# 13_-_SFP_MODULES.net
KiCad netlist of a schematic drawn in Altium Designer
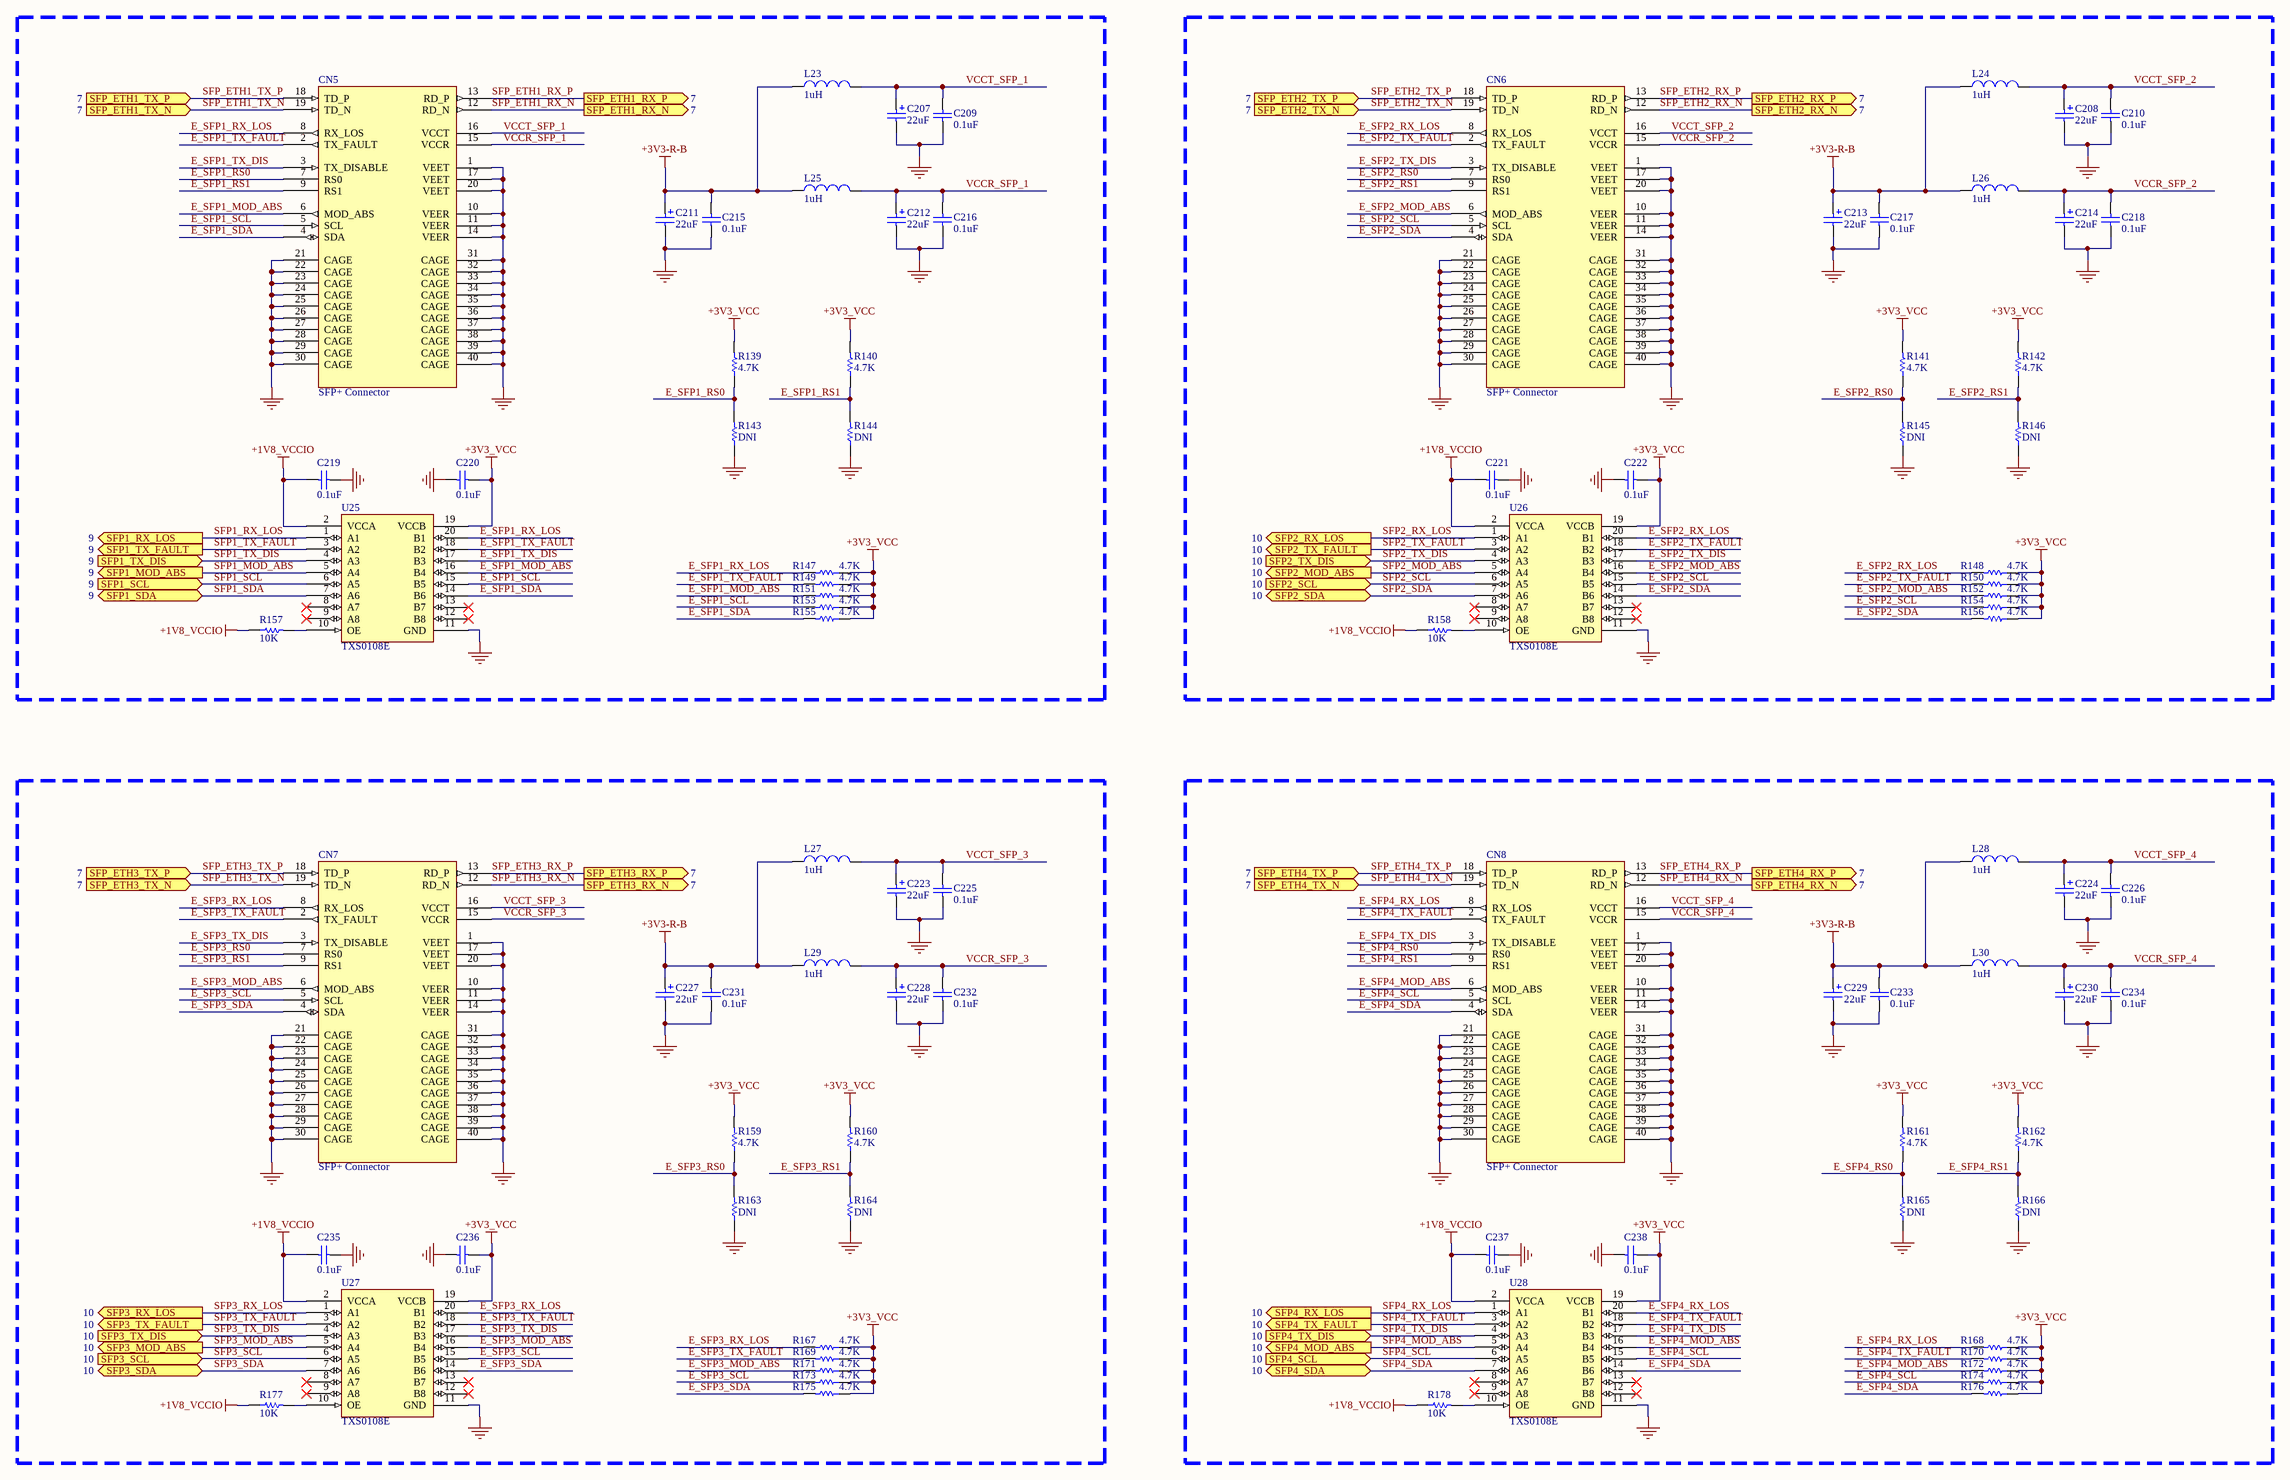
[diagram p0: [13] - SFP+ MODULES.SchDoc]

(export (version "E")
  (design (tool "Eeschema 10.0.6"))
  (components
    (comp (ref "C207")
      (value "22uF")
      (footprint "WCAP-ASLL_8x10.5")
      (description "Aluminium Electrolytic Capacitor")
      (libsource (lib "Passive Components") (part "Cap Aluminium Electrolytic"))
    )
    (comp (ref "C208")
      (value "22uF")
      (footprint "WCAP-ASLL_8x10.5")
      (description "Aluminium Electrolytic Capacitor")
      (libsource (lib "Passive Components") (part "Cap Aluminium Electrolytic"))
    )
    (comp (ref "C209")
      (value "0.1uF")
      (footprint "0402_C")
      (description "Non-Pol SMD Capacitor")
      (libsource (lib "Passive Components") (part "Cap SMD"))
    )
    (comp (ref "C210")
      (value "0.1uF")
      (footprint "0402_C")
      (description "Non-Pol SMD Capacitor")
      (libsource (lib "Passive Components") (part "Cap SMD"))
    )
    (comp (ref "C211")
      (value "22uF")
      (footprint "WCAP-ASLL_8x10.5")
      (description "Aluminium Electrolytic Capacitor")
      (libsource (lib "Passive Components") (part "Cap Aluminium Electrolytic"))
    )
    (comp (ref "C212")
      (value "22uF")
      (footprint "WCAP-ASLL_8x10.5")
      (description "Aluminium Electrolytic Capacitor")
      (libsource (lib "Passive Components") (part "Cap Aluminium Electrolytic"))
    )
    (comp (ref "C213")
      (value "22uF")
      (footprint "WCAP-ASLL_8x10.5")
      (description "Aluminium Electrolytic Capacitor")
      (libsource (lib "Passive Components") (part "Cap Aluminium Electrolytic"))
    )
    (comp (ref "C214")
      (value "22uF")
      (footprint "WCAP-ASLL_8x10.5")
      (description "Aluminium Electrolytic Capacitor")
      (libsource (lib "Passive Components") (part "Cap Aluminium Electrolytic"))
    )
    (comp (ref "C215")
      (value "0.1uF")
      (footprint "0402_C")
      (description "Non-Pol SMD Capacitor")
      (libsource (lib "Passive Components") (part "Cap SMD"))
    )
    (comp (ref "C216")
      (value "0.1uF")
      (footprint "0402_C")
      (description "Non-Pol SMD Capacitor")
      (libsource (lib "Passive Components") (part "Cap SMD"))
    )
    (comp (ref "C217")
      (value "0.1uF")
      (footprint "0402_C")
      (description "Non-Pol SMD Capacitor")
      (libsource (lib "Passive Components") (part "Cap SMD"))
    )
    (comp (ref "C218")
      (value "0.1uF")
      (footprint "0402_C")
      (description "Non-Pol SMD Capacitor")
      (libsource (lib "Passive Components") (part "Cap SMD"))
    )
    (comp (ref "C219")
      (value "0.1uF")
      (footprint "0402_C")
      (description "Non-Pol SMD Capacitor")
      (libsource (lib "Passive Components") (part "Cap SMD"))
    )
    (comp (ref "C220")
      (value "0.1uF")
      (footprint "0402_C")
      (description "Non-Pol SMD Capacitor")
      (libsource (lib "Passive Components") (part "Cap SMD"))
    )
    (comp (ref "C221")
      (value "0.1uF")
      (footprint "0402_C")
      (description "Non-Pol SMD Capacitor")
      (libsource (lib "Passive Components") (part "Cap SMD"))
    )
    (comp (ref "C222")
      (value "0.1uF")
      (footprint "0402_C")
      (description "Non-Pol SMD Capacitor")
      (libsource (lib "Passive Components") (part "Cap SMD"))
    )
    (comp (ref "C223")
      (value "22uF")
      (footprint "WCAP-ASLL_8x10.5")
      (description "Aluminium Electrolytic Capacitor")
      (libsource (lib "Passive Components") (part "Cap Aluminium Electrolytic"))
    )
    (comp (ref "C224")
      (value "22uF")
      (footprint "WCAP-ASLL_8x10.5")
      (description "Aluminium Electrolytic Capacitor")
      (libsource (lib "Passive Components") (part "Cap Aluminium Electrolytic"))
    )
    (comp (ref "C225")
      (value "0.1uF")
      (footprint "0402_C")
      (description "Non-Pol SMD Capacitor")
      (libsource (lib "Passive Components") (part "Cap SMD"))
    )
    (comp (ref "C226")
      (value "0.1uF")
      (footprint "0402_C")
      (description "Non-Pol SMD Capacitor")
      (libsource (lib "Passive Components") (part "Cap SMD"))
    )
    (comp (ref "C227")
      (value "22uF")
      (footprint "WCAP-ASLL_8x10.5")
      (description "Aluminium Electrolytic Capacitor")
      (libsource (lib "Passive Components") (part "Cap Aluminium Electrolytic"))
    )
    (comp (ref "C228")
      (value "22uF")
      (footprint "WCAP-ASLL_8x10.5")
      (description "Aluminium Electrolytic Capacitor")
      (libsource (lib "Passive Components") (part "Cap Aluminium Electrolytic"))
    )
    (comp (ref "C229")
      (value "22uF")
      (footprint "WCAP-ASLL_8x10.5")
      (description "Aluminium Electrolytic Capacitor")
      (libsource (lib "Passive Components") (part "Cap Aluminium Electrolytic"))
    )
    (comp (ref "C230")
      (value "22uF")
      (footprint "WCAP-ASLL_8x10.5")
      (description "Aluminium Electrolytic Capacitor")
      (libsource (lib "Passive Components") (part "Cap Aluminium Electrolytic"))
    )
    (comp (ref "C231")
      (value "0.1uF")
      (footprint "0402_C")
      (description "Non-Pol SMD Capacitor")
      (libsource (lib "Passive Components") (part "Cap SMD"))
    )
    (comp (ref "C232")
      (value "0.1uF")
      (footprint "0402_C")
      (description "Non-Pol SMD Capacitor")
      (libsource (lib "Passive Components") (part "Cap SMD"))
    )
    (comp (ref "C233")
      (value "0.1uF")
      (footprint "0402_C")
      (description "Non-Pol SMD Capacitor")
      (libsource (lib "Passive Components") (part "Cap SMD"))
    )
    (comp (ref "C234")
      (value "0.1uF")
      (footprint "0402_C")
      (description "Non-Pol SMD Capacitor")
      (libsource (lib "Passive Components") (part "Cap SMD"))
    )
    (comp (ref "C235")
      (value "0.1uF")
      (footprint "0402_C")
      (description "Non-Pol SMD Capacitor")
      (libsource (lib "Passive Components") (part "Cap SMD"))
    )
    (comp (ref "C236")
      (value "0.1uF")
      (footprint "0402_C")
      (description "Non-Pol SMD Capacitor")
      (libsource (lib "Passive Components") (part "Cap SMD"))
    )
    (comp (ref "C237")
      (value "0.1uF")
      (footprint "0402_C")
      (description "Non-Pol SMD Capacitor")
      (libsource (lib "Passive Components") (part "Cap SMD"))
    )
    (comp (ref "C238")
      (value "0.1uF")
      (footprint "0402_C")
      (description "Non-Pol SMD Capacitor")
      (libsource (lib "Passive Components") (part "Cap SMD"))
    )
    (comp (ref "CN5")
      (value "SFP+ Connector")
      (description "SFP+ Host Connector, Z-Axis Pluggable, Right-Angle, Surface Mount, 20 Circuits , and EMI Cage")
      (libsource (lib "Project_schlib") (part "SFP+ Connector"))
    )
    (comp (ref "CN6")
      (value "SFP+ Connector")
      (description "SFP+ Host Connector, Z-Axis Pluggable, Right-Angle, Surface Mount, 20 Circuits , and EMI Cage")
      (libsource (lib "Project_schlib") (part "SFP+ Connector"))
    )
    (comp (ref "CN7")
      (value "SFP+ Connector")
      (description "SFP+ Host Connector, Z-Axis Pluggable, Right-Angle, Surface Mount, 20 Circuits , and EMI Cage")
      (libsource (lib "Project_schlib") (part "SFP+ Connector"))
    )
    (comp (ref "CN8")
      (value "SFP+ Connector")
      (description "SFP+ Host Connector, Z-Axis Pluggable, Right-Angle, Surface Mount, 20 Circuits , and EMI Cage")
      (libsource (lib "Project_schlib") (part "SFP+ Connector"))
    )
    (comp (ref "L23")
      (value "1uH")
      (footprint "0402_R")
      (description "Inductor SMD")
      (libsource (lib "Passive Components") (part "Inductor"))
    )
    (comp (ref "L24")
      (value "1uH")
      (footprint "0402_R")
      (description "Inductor SMD")
      (libsource (lib "Passive Components") (part "Inductor"))
    )
    (comp (ref "L25")
      (value "1uH")
      (footprint "0402_R")
      (description "Inductor SMD")
      (libsource (lib "Passive Components") (part "Inductor"))
    )
    (comp (ref "L26")
      (value "1uH")
      (footprint "0402_R")
      (description "Inductor SMD")
      (libsource (lib "Passive Components") (part "Inductor"))
    )
    (comp (ref "L27")
      (value "1uH")
      (footprint "0402_R")
      (description "Inductor SMD")
      (libsource (lib "Passive Components") (part "Inductor"))
    )
    (comp (ref "L28")
      (value "1uH")
      (footprint "0402_R")
      (description "Inductor SMD")
      (libsource (lib "Passive Components") (part "Inductor"))
    )
    (comp (ref "L29")
      (value "1uH")
      (footprint "0402_R")
      (description "Inductor SMD")
      (libsource (lib "Passive Components") (part "Inductor"))
    )
    (comp (ref "L30")
      (value "1uH")
      (footprint "0402_R")
      (description "Inductor SMD")
      (libsource (lib "Passive Components") (part "Inductor"))
    )
    (comp (ref "R139")
      (value "4.7K")
      (footprint "0805_R")
      (description "SMD Resistor")
      (fields (field (name "TOLERANCE") "5%"))
      (libsource (lib "Passive Components") (part "Res SMD"))
    )
    (comp (ref "R140")
      (value "4.7K")
      (footprint "0805_R")
      (description "SMD Resistor")
      (fields (field (name "TOLERANCE") "5%"))
      (libsource (lib "Passive Components") (part "Res SMD"))
    )
    (comp (ref "R141")
      (value "4.7K")
      (footprint "0805_R")
      (description "SMD Resistor")
      (fields (field (name "TOLERANCE") "5%"))
      (libsource (lib "Passive Components") (part "Res SMD"))
    )
    (comp (ref "R142")
      (value "4.7K")
      (footprint "0805_R")
      (description "SMD Resistor")
      (fields (field (name "TOLERANCE") "5%"))
      (libsource (lib "Passive Components") (part "Res SMD"))
    )
    (comp (ref "R143")
      (value "DNI")
      (footprint "0805_R")
      (description "SMD Resistor")
      (fields (field (name "TOLERANCE") "5%"))
      (libsource (lib "Passive Components") (part "Res SMD"))
    )
    (comp (ref "R144")
      (value "DNI")
      (footprint "0805_R")
      (description "SMD Resistor")
      (fields (field (name "TOLERANCE") "5%"))
      (libsource (lib "Passive Components") (part "Res SMD"))
    )
    (comp (ref "R145")
      (value "DNI")
      (footprint "0805_R")
      (description "SMD Resistor")
      (fields (field (name "TOLERANCE") "5%"))
      (libsource (lib "Passive Components") (part "Res SMD"))
    )
    (comp (ref "R146")
      (value "DNI")
      (footprint "0805_R")
      (description "SMD Resistor")
      (fields (field (name "TOLERANCE") "5%"))
      (libsource (lib "Passive Components") (part "Res SMD"))
    )
    (comp (ref "R147")
      (value "4.7K")
      (footprint "0805_R")
      (description "SMD Resistor")
      (fields (field (name "TOLERANCE") "5%"))
      (libsource (lib "Passive Components") (part "Res SMD"))
    )
    (comp (ref "R148")
      (value "4.7K")
      (footprint "0805_R")
      (description "SMD Resistor")
      (fields (field (name "TOLERANCE") "5%"))
      (libsource (lib "Passive Components") (part "Res SMD"))
    )
    (comp (ref "R149")
      (value "4.7K")
      (footprint "0805_R")
      (description "SMD Resistor")
      (fields (field (name "TOLERANCE") "5%"))
      (libsource (lib "Passive Components") (part "Res SMD"))
    )
    (comp (ref "R150")
      (value "4.7K")
      (footprint "0805_R")
      (description "SMD Resistor")
      (fields (field (name "TOLERANCE") "5%"))
      (libsource (lib "Passive Components") (part "Res SMD"))
    )
    (comp (ref "R151")
      (value "4.7K")
      (footprint "0805_R")
      (description "SMD Resistor")
      (fields (field (name "TOLERANCE") "5%"))
      (libsource (lib "Passive Components") (part "Res SMD"))
    )
    (comp (ref "R152")
      (value "4.7K")
      (footprint "0805_R")
      (description "SMD Resistor")
      (fields (field (name "TOLERANCE") "5%"))
      (libsource (lib "Passive Components") (part "Res SMD"))
    )
    (comp (ref "R153")
      (value "4.7K")
      (footprint "0805_R")
      (description "SMD Resistor")
      (fields (field (name "TOLERANCE") "5%"))
      (libsource (lib "Passive Components") (part "Res SMD"))
    )
    (comp (ref "R154")
      (value "4.7K")
      (footprint "0805_R")
      (description "SMD Resistor")
      (fields (field (name "TOLERANCE") "5%"))
      (libsource (lib "Passive Components") (part "Res SMD"))
    )
    (comp (ref "R155")
      (value "4.7K")
      (footprint "0805_R")
      (description "SMD Resistor")
      (fields (field (name "TOLERANCE") "5%"))
      (libsource (lib "Passive Components") (part "Res SMD"))
    )
    (comp (ref "R156")
      (value "4.7K")
      (footprint "0805_R")
      (description "SMD Resistor")
      (fields (field (name "TOLERANCE") "5%"))
      (libsource (lib "Passive Components") (part "Res SMD"))
    )
    (comp (ref "R157")
      (value "10K")
      (footprint "0402_R")
      (description "SMD Resistor")
      (fields (field (name "TOLERANCE") "5%"))
      (libsource (lib "Passive Components") (part "Res SMD"))
    )
    (comp (ref "R158")
      (value "10K")
      (footprint "0402_R")
      (description "SMD Resistor")
      (fields (field (name "TOLERANCE") "5%"))
      (libsource (lib "Passive Components") (part "Res SMD"))
    )
    (comp (ref "R159")
      (value "4.7K")
      (footprint "0805_R")
      (description "SMD Resistor")
      (fields (field (name "TOLERANCE") "5%"))
      (libsource (lib "Passive Components") (part "Res SMD"))
    )
    (comp (ref "R160")
      (value "4.7K")
      (footprint "0805_R")
      (description "SMD Resistor")
      (fields (field (name "TOLERANCE") "5%"))
      (libsource (lib "Passive Components") (part "Res SMD"))
    )
    (comp (ref "R161")
      (value "4.7K")
      (footprint "0805_R")
      (description "SMD Resistor")
      (fields (field (name "TOLERANCE") "5%"))
      (libsource (lib "Passive Components") (part "Res SMD"))
    )
    (comp (ref "R162")
      (value "4.7K")
      (footprint "0805_R")
      (description "SMD Resistor")
      (fields (field (name "TOLERANCE") "5%"))
      (libsource (lib "Passive Components") (part "Res SMD"))
    )
    (comp (ref "R163")
      (value "DNI")
      (footprint "0805_R")
      (description "SMD Resistor")
      (fields (field (name "TOLERANCE") "5%"))
      (libsource (lib "Passive Components") (part "Res SMD"))
    )
    (comp (ref "R164")
      (value "DNI")
      (footprint "0805_R")
      (description "SMD Resistor")
      (fields (field (name "TOLERANCE") "5%"))
      (libsource (lib "Passive Components") (part "Res SMD"))
    )
    (comp (ref "R165")
      (value "DNI")
      (footprint "0805_R")
      (description "SMD Resistor")
      (fields (field (name "TOLERANCE") "5%"))
      (libsource (lib "Passive Components") (part "Res SMD"))
    )
    (comp (ref "R166")
      (value "DNI")
      (footprint "0805_R")
      (description "SMD Resistor")
      (fields (field (name "TOLERANCE") "5%"))
      (libsource (lib "Passive Components") (part "Res SMD"))
    )
    (comp (ref "R167")
      (value "4.7K")
      (footprint "0805_R")
      (description "SMD Resistor")
      (fields (field (name "TOLERANCE") "5%"))
      (libsource (lib "Passive Components") (part "Res SMD"))
    )
    (comp (ref "R168")
      (value "4.7K")
      (footprint "0805_R")
      (description "SMD Resistor")
      (fields (field (name "TOLERANCE") "5%"))
      (libsource (lib "Passive Components") (part "Res SMD"))
    )
    (comp (ref "R169")
      (value "4.7K")
      (footprint "0805_R")
      (description "SMD Resistor")
      (fields (field (name "TOLERANCE") "5%"))
      (libsource (lib "Passive Components") (part "Res SMD"))
    )
    (comp (ref "R170")
      (value "4.7K")
      (footprint "0805_R")
      (description "SMD Resistor")
      (fields (field (name "TOLERANCE") "5%"))
      (libsource (lib "Passive Components") (part "Res SMD"))
    )
    (comp (ref "R171")
      (value "4.7K")
      (footprint "0805_R")
      (description "SMD Resistor")
      (fields (field (name "TOLERANCE") "5%"))
      (libsource (lib "Passive Components") (part "Res SMD"))
    )
    (comp (ref "R172")
      (value "4.7K")
      (footprint "0805_R")
      (description "SMD Resistor")
      (fields (field (name "TOLERANCE") "5%"))
      (libsource (lib "Passive Components") (part "Res SMD"))
    )
    (comp (ref "R173")
      (value "4.7K")
      (footprint "0805_R")
      (description "SMD Resistor")
      (fields (field (name "TOLERANCE") "5%"))
      (libsource (lib "Passive Components") (part "Res SMD"))
    )
    (comp (ref "R174")
      (value "4.7K")
      (footprint "0805_R")
      (description "SMD Resistor")
      (fields (field (name "TOLERANCE") "5%"))
      (libsource (lib "Passive Components") (part "Res SMD"))
    )
    (comp (ref "R175")
      (value "4.7K")
      (footprint "0805_R")
      (description "SMD Resistor")
      (fields (field (name "TOLERANCE") "5%"))
      (libsource (lib "Passive Components") (part "Res SMD"))
    )
    (comp (ref "R176")
      (value "4.7K")
      (footprint "0805_R")
      (description "SMD Resistor")
      (fields (field (name "TOLERANCE") "5%"))
      (libsource (lib "Passive Components") (part "Res SMD"))
    )
    (comp (ref "R177")
      (value "10K")
      (footprint "0402_R")
      (description "SMD Resistor")
      (fields (field (name "TOLERANCE") "5%"))
      (libsource (lib "Passive Components") (part "Res SMD"))
    )
    (comp (ref "R178")
      (value "10K")
      (footprint "0402_R")
      (description "SMD Resistor")
      (fields (field (name "TOLERANCE") "5%"))
      (libsource (lib "Passive Components") (part "Res SMD"))
    )
    (comp (ref "U25")
      (value "TXS0108E")
      (description "8-Bit Bidirectional Voltage-Level Translator for Open-Drain and Push-Pull Applications")
      (fields (field (name "MANUFACTURER PART NUM") "TXS0108EPWR"))
      (libsource (lib "Project_schlib") (part "TXS0108E"))
    )
    (comp (ref "U26")
      (value "TXS0108E")
      (description "8-Bit Bidirectional Voltage-Level Translator for Open-Drain and Push-Pull Applications")
      (fields (field (name "MANUFACTURER PART NUM") "TXS0108EPWR"))
      (libsource (lib "Project_schlib") (part "TXS0108E"))
    )
    (comp (ref "U27")
      (value "TXS0108E")
      (description "8-Bit Bidirectional Voltage-Level Translator for Open-Drain and Push-Pull Applications")
      (fields (field (name "MANUFACTURER PART NUM") "TXS0108EPWR"))
      (libsource (lib "Project_schlib") (part "TXS0108E"))
    )
    (comp (ref "U28")
      (value "TXS0108E")
      (description "8-Bit Bidirectional Voltage-Level Translator for Open-Drain and Push-Pull Applications")
      (fields (field (name "MANUFACTURER PART NUM") "TXS0108EPWR"))
      (libsource (lib "Project_schlib") (part "TXS0108E"))
    )
  )
  (nets
    (net (code "1") (name "+1V8_VCCIO") (class "Default")
      (node (ref "C219") (pin "2") (pinfunction "2_2") (pintype "passive"))
      (node (ref "C221") (pin "2") (pinfunction "2_2") (pintype "passive"))
      (node (ref "C235") (pin "2") (pinfunction "2_2") (pintype "passive"))
      (node (ref "C237") (pin "2") (pinfunction "2_2") (pintype "passive"))
      (node (ref "R157") (pin "1") (pinfunction "1_1") (pintype "passive"))
      (node (ref "R158") (pin "1") (pinfunction "1_1") (pintype "passive"))
      (node (ref "R177") (pin "1") (pinfunction "1_1") (pintype "passive"))
      (node (ref "R178") (pin "1") (pinfunction "1_1") (pintype "passive"))
      (node (ref "U25") (pin "2") (pinfunction "VCCA_2") (pintype "power_in"))
      (node (ref "U26") (pin "2") (pinfunction "VCCA_2") (pintype "power_in"))
      (node (ref "U27") (pin "2") (pinfunction "VCCA_2") (pintype "power_in"))
      (node (ref "U28") (pin "2") (pinfunction "VCCA_2") (pintype "power_in"))
    )
    (net (code "2") (name "+3V3-R-B") (class "Default")
      (node (ref "C211") (pin "1") (pinfunction "1_1") (pintype "passive"))
      (node (ref "C213") (pin "1") (pinfunction "1_1") (pintype "passive"))
      (node (ref "C215") (pin "1") (pinfunction "1_1") (pintype "passive"))
      (node (ref "C217") (pin "1") (pinfunction "1_1") (pintype "passive"))
      (node (ref "C227") (pin "1") (pinfunction "1_1") (pintype "passive"))
      (node (ref "C229") (pin "1") (pinfunction "1_1") (pintype "passive"))
      (node (ref "C231") (pin "1") (pinfunction "1_1") (pintype "passive"))
      (node (ref "C233") (pin "1") (pinfunction "1_1") (pintype "passive"))
      (node (ref "L23") (pin "1") (pinfunction "1_1") (pintype "passive"))
      (node (ref "L24") (pin "1") (pinfunction "1_1") (pintype "passive"))
      (node (ref "L25") (pin "1") (pinfunction "1_1") (pintype "passive"))
      (node (ref "L26") (pin "1") (pinfunction "1_1") (pintype "passive"))
      (node (ref "L27") (pin "1") (pinfunction "1_1") (pintype "passive"))
      (node (ref "L28") (pin "1") (pinfunction "1_1") (pintype "passive"))
      (node (ref "L29") (pin "1") (pinfunction "1_1") (pintype "passive"))
      (node (ref "L30") (pin "1") (pinfunction "1_1") (pintype "passive"))
    )
    (net (code "3") (name "+3V3_VCC") (class "Default")
      (node (ref "C220") (pin "1") (pinfunction "1_1") (pintype "passive"))
      (node (ref "C222") (pin "1") (pinfunction "1_1") (pintype "passive"))
      (node (ref "C236") (pin "1") (pinfunction "1_1") (pintype "passive"))
      (node (ref "C238") (pin "1") (pinfunction "1_1") (pintype "passive"))
      (node (ref "R139") (pin "2") (pinfunction "2_2") (pintype "passive"))
      (node (ref "R140") (pin "2") (pinfunction "2_2") (pintype "passive"))
      (node (ref "R141") (pin "2") (pinfunction "2_2") (pintype "passive"))
      (node (ref "R142") (pin "2") (pinfunction "2_2") (pintype "passive"))
      (node (ref "R147") (pin "1") (pinfunction "1_1") (pintype "passive"))
      (node (ref "R148") (pin "1") (pinfunction "1_1") (pintype "passive"))
      (node (ref "R149") (pin "1") (pinfunction "1_1") (pintype "passive"))
      (node (ref "R150") (pin "1") (pinfunction "1_1") (pintype "passive"))
      (node (ref "R151") (pin "1") (pinfunction "1_1") (pintype "passive"))
      (node (ref "R152") (pin "1") (pinfunction "1_1") (pintype "passive"))
      (node (ref "R153") (pin "1") (pinfunction "1_1") (pintype "passive"))
      (node (ref "R154") (pin "1") (pinfunction "1_1") (pintype "passive"))
      (node (ref "R155") (pin "1") (pinfunction "1_1") (pintype "passive"))
      (node (ref "R156") (pin "1") (pinfunction "1_1") (pintype "passive"))
      (node (ref "R159") (pin "2") (pinfunction "2_2") (pintype "passive"))
      (node (ref "R160") (pin "2") (pinfunction "2_2") (pintype "passive"))
      (node (ref "R161") (pin "2") (pinfunction "2_2") (pintype "passive"))
      (node (ref "R162") (pin "2") (pinfunction "2_2") (pintype "passive"))
      (node (ref "R167") (pin "1") (pinfunction "1_1") (pintype "passive"))
      (node (ref "R168") (pin "1") (pinfunction "1_1") (pintype "passive"))
      (node (ref "R169") (pin "1") (pinfunction "1_1") (pintype "passive"))
      (node (ref "R170") (pin "1") (pinfunction "1_1") (pintype "passive"))
      (node (ref "R171") (pin "1") (pinfunction "1_1") (pintype "passive"))
      (node (ref "R172") (pin "1") (pinfunction "1_1") (pintype "passive"))
      (node (ref "R173") (pin "1") (pinfunction "1_1") (pintype "passive"))
      (node (ref "R174") (pin "1") (pinfunction "1_1") (pintype "passive"))
      (node (ref "R175") (pin "1") (pinfunction "1_1") (pintype "passive"))
      (node (ref "R176") (pin "1") (pinfunction "1_1") (pintype "passive"))
      (node (ref "U25") (pin "19") (pinfunction "VCCB_19") (pintype "power_in"))
      (node (ref "U26") (pin "19") (pinfunction "VCCB_19") (pintype "power_in"))
      (node (ref "U27") (pin "19") (pinfunction "VCCB_19") (pintype "power_in"))
      (node (ref "U28") (pin "19") (pinfunction "VCCB_19") (pintype "power_in"))
    )
    (net (code "4") (name "/E_SFP1_MOD_ABS") (class "Default")
      (node (ref "CN5") (pin "6") (pinfunction "MOD_ABS_6") (pintype "output"))
      (node (ref "R151") (pin "2") (pinfunction "2_2") (pintype "passive"))
      (node (ref "U25") (pin "16") (pinfunction "B4_16") (pintype "bidirectional"))
    )
    (net (code "5") (name "/E_SFP1_RS0") (class "Default")
      (node (ref "CN5") (pin "7") (pinfunction "RS0_7") (pintype "passive"))
      (node (ref "R139") (pin "1") (pinfunction "1_1") (pintype "passive"))
      (node (ref "R143") (pin "2") (pinfunction "2_2") (pintype "passive"))
    )
    (net (code "6") (name "/E_SFP1_RS1") (class "Default")
      (node (ref "CN5") (pin "9") (pinfunction "RS1_9") (pintype "passive"))
      (node (ref "R140") (pin "1") (pinfunction "1_1") (pintype "passive"))
      (node (ref "R144") (pin "2") (pinfunction "2_2") (pintype "passive"))
    )
    (net (code "7") (name "/E_SFP1_RX_LOS") (class "Default")
      (node (ref "CN5") (pin "8") (pinfunction "RX_LOS_8") (pintype "output"))
      (node (ref "R147") (pin "2") (pinfunction "2_2") (pintype "passive"))
      (node (ref "U25") (pin "20") (pinfunction "B1_20") (pintype "bidirectional"))
    )
    (net (code "8") (name "/E_SFP1_SCL") (class "Default")
      (node (ref "CN5") (pin "5") (pinfunction "SCL_5") (pintype "input"))
      (node (ref "R153") (pin "2") (pinfunction "2_2") (pintype "passive"))
      (node (ref "U25") (pin "15") (pinfunction "B5_15") (pintype "bidirectional"))
    )
    (net (code "9") (name "/E_SFP1_SDA") (class "Default")
      (node (ref "CN5") (pin "4") (pinfunction "SDA_4") (pintype "bidirectional"))
      (node (ref "R155") (pin "2") (pinfunction "2_2") (pintype "passive"))
      (node (ref "U25") (pin "14") (pinfunction "B6_14") (pintype "bidirectional"))
    )
    (net (code "10") (name "/E_SFP1_TX_DIS") (class "Default")
      (node (ref "CN5") (pin "3") (pinfunction "TX_DISABLE_3") (pintype "input"))
      (node (ref "U25") (pin "17") (pinfunction "B3_17") (pintype "bidirectional"))
    )
    (net (code "11") (name "/E_SFP1_TX_FAULT") (class "Default")
      (node (ref "CN5") (pin "2") (pinfunction "TX_FAULT_2") (pintype "output"))
      (node (ref "R149") (pin "2") (pinfunction "2_2") (pintype "passive"))
      (node (ref "U25") (pin "18") (pinfunction "B2_18") (pintype "bidirectional"))
    )
    (net (code "12") (name "/E_SFP2_MOD_ABS") (class "Default")
      (node (ref "CN6") (pin "6") (pinfunction "MOD_ABS_6") (pintype "output"))
      (node (ref "R152") (pin "2") (pinfunction "2_2") (pintype "passive"))
      (node (ref "U26") (pin "16") (pinfunction "B4_16") (pintype "bidirectional"))
    )
    (net (code "13") (name "/E_SFP2_RS0") (class "Default")
      (node (ref "CN6") (pin "7") (pinfunction "RS0_7") (pintype "passive"))
      (node (ref "R141") (pin "1") (pinfunction "1_1") (pintype "passive"))
      (node (ref "R145") (pin "2") (pinfunction "2_2") (pintype "passive"))
    )
    (net (code "14") (name "/E_SFP2_RS1") (class "Default")
      (node (ref "CN6") (pin "9") (pinfunction "RS1_9") (pintype "passive"))
      (node (ref "R142") (pin "1") (pinfunction "1_1") (pintype "passive"))
      (node (ref "R146") (pin "2") (pinfunction "2_2") (pintype "passive"))
    )
    (net (code "15") (name "/E_SFP2_RX_LOS") (class "Default")
      (node (ref "CN6") (pin "8") (pinfunction "RX_LOS_8") (pintype "output"))
      (node (ref "R148") (pin "2") (pinfunction "2_2") (pintype "passive"))
      (node (ref "U26") (pin "20") (pinfunction "B1_20") (pintype "bidirectional"))
    )
    (net (code "16") (name "/E_SFP2_SCL") (class "Default")
      (node (ref "CN6") (pin "5") (pinfunction "SCL_5") (pintype "input"))
      (node (ref "R154") (pin "2") (pinfunction "2_2") (pintype "passive"))
      (node (ref "U26") (pin "15") (pinfunction "B5_15") (pintype "bidirectional"))
    )
    (net (code "17") (name "/E_SFP2_SDA") (class "Default")
      (node (ref "CN6") (pin "4") (pinfunction "SDA_4") (pintype "bidirectional"))
      (node (ref "R156") (pin "2") (pinfunction "2_2") (pintype "passive"))
      (node (ref "U26") (pin "14") (pinfunction "B6_14") (pintype "bidirectional"))
    )
    (net (code "18") (name "/E_SFP2_TX_DIS") (class "Default")
      (node (ref "CN6") (pin "3") (pinfunction "TX_DISABLE_3") (pintype "input"))
      (node (ref "U26") (pin "17") (pinfunction "B3_17") (pintype "bidirectional"))
    )
    (net (code "19") (name "/E_SFP2_TX_FAULT") (class "Default")
      (node (ref "CN6") (pin "2") (pinfunction "TX_FAULT_2") (pintype "output"))
      (node (ref "R150") (pin "2") (pinfunction "2_2") (pintype "passive"))
      (node (ref "U26") (pin "18") (pinfunction "B2_18") (pintype "bidirectional"))
    )
    (net (code "20") (name "/E_SFP3_MOD_ABS") (class "Default")
      (node (ref "CN7") (pin "6") (pinfunction "MOD_ABS_6") (pintype "output"))
      (node (ref "R171") (pin "2") (pinfunction "2_2") (pintype "passive"))
      (node (ref "U27") (pin "16") (pinfunction "B4_16") (pintype "bidirectional"))
    )
    (net (code "21") (name "/E_SFP3_RS0") (class "Default")
      (node (ref "CN7") (pin "7") (pinfunction "RS0_7") (pintype "passive"))
      (node (ref "R159") (pin "1") (pinfunction "1_1") (pintype "passive"))
      (node (ref "R163") (pin "2") (pinfunction "2_2") (pintype "passive"))
    )
    (net (code "22") (name "/E_SFP3_RS1") (class "Default")
      (node (ref "CN7") (pin "9") (pinfunction "RS1_9") (pintype "passive"))
      (node (ref "R160") (pin "1") (pinfunction "1_1") (pintype "passive"))
      (node (ref "R164") (pin "2") (pinfunction "2_2") (pintype "passive"))
    )
    (net (code "23") (name "/E_SFP3_RX_LOS") (class "Default")
      (node (ref "CN7") (pin "8") (pinfunction "RX_LOS_8") (pintype "output"))
      (node (ref "R167") (pin "2") (pinfunction "2_2") (pintype "passive"))
      (node (ref "U27") (pin "20") (pinfunction "B1_20") (pintype "bidirectional"))
    )
    (net (code "24") (name "/E_SFP3_SCL") (class "Default")
      (node (ref "CN7") (pin "5") (pinfunction "SCL_5") (pintype "input"))
      (node (ref "R173") (pin "2") (pinfunction "2_2") (pintype "passive"))
      (node (ref "U27") (pin "15") (pinfunction "B5_15") (pintype "bidirectional"))
    )
    (net (code "25") (name "/E_SFP3_SDA") (class "Default")
      (node (ref "CN7") (pin "4") (pinfunction "SDA_4") (pintype "bidirectional"))
      (node (ref "R175") (pin "2") (pinfunction "2_2") (pintype "passive"))
      (node (ref "U27") (pin "14") (pinfunction "B6_14") (pintype "bidirectional"))
    )
    (net (code "26") (name "/E_SFP3_TX_DIS") (class "Default")
      (node (ref "CN7") (pin "3") (pinfunction "TX_DISABLE_3") (pintype "input"))
      (node (ref "U27") (pin "17") (pinfunction "B3_17") (pintype "bidirectional"))
    )
    (net (code "27") (name "/E_SFP3_TX_FAULT") (class "Default")
      (node (ref "CN7") (pin "2") (pinfunction "TX_FAULT_2") (pintype "output"))
      (node (ref "R169") (pin "2") (pinfunction "2_2") (pintype "passive"))
      (node (ref "U27") (pin "18") (pinfunction "B2_18") (pintype "bidirectional"))
    )
    (net (code "28") (name "/E_SFP4_MOD_ABS") (class "Default")
      (node (ref "CN8") (pin "6") (pinfunction "MOD_ABS_6") (pintype "output"))
      (node (ref "R172") (pin "2") (pinfunction "2_2") (pintype "passive"))
      (node (ref "U28") (pin "16") (pinfunction "B4_16") (pintype "bidirectional"))
    )
    (net (code "29") (name "/E_SFP4_RS0") (class "Default")
      (node (ref "CN8") (pin "7") (pinfunction "RS0_7") (pintype "passive"))
      (node (ref "R161") (pin "1") (pinfunction "1_1") (pintype "passive"))
      (node (ref "R165") (pin "2") (pinfunction "2_2") (pintype "passive"))
    )
    (net (code "30") (name "/E_SFP4_RS1") (class "Default")
      (node (ref "CN8") (pin "9") (pinfunction "RS1_9") (pintype "passive"))
      (node (ref "R162") (pin "1") (pinfunction "1_1") (pintype "passive"))
      (node (ref "R166") (pin "2") (pinfunction "2_2") (pintype "passive"))
    )
    (net (code "31") (name "/E_SFP4_RX_LOS") (class "Default")
      (node (ref "CN8") (pin "8") (pinfunction "RX_LOS_8") (pintype "output"))
      (node (ref "R168") (pin "2") (pinfunction "2_2") (pintype "passive"))
      (node (ref "U28") (pin "20") (pinfunction "B1_20") (pintype "bidirectional"))
    )
    (net (code "32") (name "/E_SFP4_SCL") (class "Default")
      (node (ref "CN8") (pin "5") (pinfunction "SCL_5") (pintype "input"))
      (node (ref "R174") (pin "2") (pinfunction "2_2") (pintype "passive"))
      (node (ref "U28") (pin "15") (pinfunction "B5_15") (pintype "bidirectional"))
    )
    (net (code "33") (name "/E_SFP4_SDA") (class "Default")
      (node (ref "CN8") (pin "4") (pinfunction "SDA_4") (pintype "bidirectional"))
      (node (ref "R176") (pin "2") (pinfunction "2_2") (pintype "passive"))
      (node (ref "U28") (pin "14") (pinfunction "B6_14") (pintype "bidirectional"))
    )
    (net (code "34") (name "/E_SFP4_TX_DIS") (class "Default")
      (node (ref "CN8") (pin "3") (pinfunction "TX_DISABLE_3") (pintype "input"))
      (node (ref "U28") (pin "17") (pinfunction "B3_17") (pintype "bidirectional"))
    )
    (net (code "35") (name "/E_SFP4_TX_FAULT") (class "Default")
      (node (ref "CN8") (pin "2") (pinfunction "TX_FAULT_2") (pintype "output"))
      (node (ref "R170") (pin "2") (pinfunction "2_2") (pintype "passive"))
      (node (ref "U28") (pin "18") (pinfunction "B2_18") (pintype "bidirectional"))
    )
    (net (code "36") (name "/SFP1_MOD_ABS") (class "Default")
      (node (ref "U25") (pin "5") (pinfunction "A4_5") (pintype "bidirectional"))
    )
    (net (code "37") (name "/SFP1_RX_LOS") (class "Default")
      (node (ref "U25") (pin "1") (pinfunction "A1_1") (pintype "bidirectional"))
    )
    (net (code "38") (name "/SFP1_SCL") (class "Default")
      (node (ref "U25") (pin "6") (pinfunction "A5_6") (pintype "bidirectional"))
    )
    (net (code "39") (name "/SFP1_SDA") (class "Default")
      (node (ref "U25") (pin "7") (pinfunction "A6_7") (pintype "bidirectional"))
    )
    (net (code "40") (name "/SFP1_TX_DIS") (class "Default")
      (node (ref "U25") (pin "4") (pinfunction "A3_4") (pintype "bidirectional"))
    )
    (net (code "41") (name "/SFP1_TX_FAULT") (class "Default")
      (node (ref "U25") (pin "3") (pinfunction "A2_3") (pintype "bidirectional"))
    )
    (net (code "42") (name "/SFP2_MOD_ABS") (class "Default")
      (node (ref "U26") (pin "5") (pinfunction "A4_5") (pintype "bidirectional"))
    )
    (net (code "43") (name "/SFP2_RX_LOS") (class "Default")
      (node (ref "U26") (pin "1") (pinfunction "A1_1") (pintype "bidirectional"))
    )
    (net (code "44") (name "/SFP2_SCL") (class "Default")
      (node (ref "U26") (pin "6") (pinfunction "A5_6") (pintype "bidirectional"))
    )
    (net (code "45") (name "/SFP2_SDA") (class "Default")
      (node (ref "U26") (pin "7") (pinfunction "A6_7") (pintype "bidirectional"))
    )
    (net (code "46") (name "/SFP2_TX_DIS") (class "Default")
      (node (ref "U26") (pin "4") (pinfunction "A3_4") (pintype "bidirectional"))
    )
    (net (code "47") (name "/SFP2_TX_FAULT") (class "Default")
      (node (ref "U26") (pin "3") (pinfunction "A2_3") (pintype "bidirectional"))
    )
    (net (code "48") (name "/SFP3_MOD_ABS") (class "Default")
      (node (ref "U27") (pin "5") (pinfunction "A4_5") (pintype "bidirectional"))
    )
    (net (code "49") (name "/SFP3_RX_LOS") (class "Default")
      (node (ref "U27") (pin "1") (pinfunction "A1_1") (pintype "bidirectional"))
    )
    (net (code "50") (name "/SFP3_SCL") (class "Default")
      (node (ref "U27") (pin "6") (pinfunction "A5_6") (pintype "bidirectional"))
    )
    (net (code "51") (name "/SFP3_SDA") (class "Default")
      (node (ref "U27") (pin "7") (pinfunction "A6_7") (pintype "bidirectional"))
    )
    (net (code "52") (name "/SFP3_TX_DIS") (class "Default")
      (node (ref "U27") (pin "4") (pinfunction "A3_4") (pintype "bidirectional"))
    )
    (net (code "53") (name "/SFP3_TX_FAULT") (class "Default")
      (node (ref "U27") (pin "3") (pinfunction "A2_3") (pintype "bidirectional"))
    )
    (net (code "54") (name "/SFP4_MOD_ABS") (class "Default")
      (node (ref "U28") (pin "5") (pinfunction "A4_5") (pintype "bidirectional"))
    )
    (net (code "55") (name "/SFP4_RX_LOS") (class "Default")
      (node (ref "U28") (pin "1") (pinfunction "A1_1") (pintype "bidirectional"))
    )
    (net (code "56") (name "/SFP4_SCL") (class "Default")
      (node (ref "U28") (pin "6") (pinfunction "A5_6") (pintype "bidirectional"))
    )
    (net (code "57") (name "/SFP4_SDA") (class "Default")
      (node (ref "U28") (pin "7") (pinfunction "A6_7") (pintype "bidirectional"))
    )
    (net (code "58") (name "/SFP4_TX_DIS") (class "Default")
      (node (ref "U28") (pin "4") (pinfunction "A3_4") (pintype "bidirectional"))
    )
    (net (code "59") (name "/SFP4_TX_FAULT") (class "Default")
      (node (ref "U28") (pin "3") (pinfunction "A2_3") (pintype "bidirectional"))
    )
    (net (code "60") (name "/SFP_ETH1_RX_N") (class "Default")
      (node (ref "CN5") (pin "12") (pinfunction "RD_N_12") (pintype "output"))
    )
    (net (code "61") (name "/SFP_ETH1_RX_P") (class "Default")
      (node (ref "CN5") (pin "13") (pinfunction "RD_P_13") (pintype "output"))
    )
    (net (code "62") (name "/SFP_ETH1_TX_N") (class "Default")
      (node (ref "CN5") (pin "19") (pinfunction "TD_N_19") (pintype "input"))
    )
    (net (code "63") (name "/SFP_ETH1_TX_P") (class "Default")
      (node (ref "CN5") (pin "18") (pinfunction "TD_P_18") (pintype "input"))
    )
    (net (code "64") (name "/SFP_ETH2_RX_N") (class "Default")
      (node (ref "CN6") (pin "12") (pinfunction "RD_N_12") (pintype "output"))
    )
    (net (code "65") (name "/SFP_ETH2_RX_P") (class "Default")
      (node (ref "CN6") (pin "13") (pinfunction "RD_P_13") (pintype "output"))
    )
    (net (code "66") (name "/SFP_ETH2_TX_N") (class "Default")
      (node (ref "CN6") (pin "19") (pinfunction "TD_N_19") (pintype "input"))
    )
    (net (code "67") (name "/SFP_ETH2_TX_P") (class "Default")
      (node (ref "CN6") (pin "18") (pinfunction "TD_P_18") (pintype "input"))
    )
    (net (code "68") (name "/SFP_ETH3_RX_N") (class "Default")
      (node (ref "CN7") (pin "12") (pinfunction "RD_N_12") (pintype "output"))
    )
    (net (code "69") (name "/SFP_ETH3_RX_P") (class "Default")
      (node (ref "CN7") (pin "13") (pinfunction "RD_P_13") (pintype "output"))
    )
    (net (code "70") (name "/SFP_ETH3_TX_N") (class "Default")
      (node (ref "CN7") (pin "19") (pinfunction "TD_N_19") (pintype "input"))
    )
    (net (code "71") (name "/SFP_ETH3_TX_P") (class "Default")
      (node (ref "CN7") (pin "18") (pinfunction "TD_P_18") (pintype "input"))
    )
    (net (code "72") (name "/SFP_ETH4_RX_N") (class "Default")
      (node (ref "CN8") (pin "12") (pinfunction "RD_N_12") (pintype "output"))
    )
    (net (code "73") (name "/SFP_ETH4_RX_P") (class "Default")
      (node (ref "CN8") (pin "13") (pinfunction "RD_P_13") (pintype "output"))
    )
    (net (code "74") (name "/SFP_ETH4_TX_N") (class "Default")
      (node (ref "CN8") (pin "19") (pinfunction "TD_N_19") (pintype "input"))
    )
    (net (code "75") (name "/SFP_ETH4_TX_P") (class "Default")
      (node (ref "CN8") (pin "18") (pinfunction "TD_P_18") (pintype "input"))
    )
    (net (code "76") (name "/VCCR_SFP_1") (class "Default")
      (node (ref "C212") (pin "1") (pinfunction "1_1") (pintype "passive"))
      (node (ref "C216") (pin "1") (pinfunction "1_1") (pintype "passive"))
      (node (ref "CN5") (pin "15") (pinfunction "VCCR_15") (pintype "power_in"))
      (node (ref "L25") (pin "2") (pinfunction "2_2") (pintype "passive"))
    )
    (net (code "77") (name "/VCCR_SFP_2") (class "Default")
      (node (ref "C214") (pin "1") (pinfunction "1_1") (pintype "passive"))
      (node (ref "C218") (pin "1") (pinfunction "1_1") (pintype "passive"))
      (node (ref "CN6") (pin "15") (pinfunction "VCCR_15") (pintype "power_in"))
      (node (ref "L26") (pin "2") (pinfunction "2_2") (pintype "passive"))
    )
    (net (code "78") (name "/VCCR_SFP_3") (class "Default")
      (node (ref "C228") (pin "1") (pinfunction "1_1") (pintype "passive"))
      (node (ref "C232") (pin "1") (pinfunction "1_1") (pintype "passive"))
      (node (ref "CN7") (pin "15") (pinfunction "VCCR_15") (pintype "power_in"))
      (node (ref "L29") (pin "2") (pinfunction "2_2") (pintype "passive"))
    )
    (net (code "79") (name "/VCCR_SFP_4") (class "Default")
      (node (ref "C230") (pin "1") (pinfunction "1_1") (pintype "passive"))
      (node (ref "C234") (pin "1") (pinfunction "1_1") (pintype "passive"))
      (node (ref "CN8") (pin "15") (pinfunction "VCCR_15") (pintype "power_in"))
      (node (ref "L30") (pin "2") (pinfunction "2_2") (pintype "passive"))
    )
    (net (code "80") (name "/VCCT_SFP_1") (class "Default")
      (node (ref "C207") (pin "1") (pinfunction "1_1") (pintype "passive"))
      (node (ref "C209") (pin "1") (pinfunction "1_1") (pintype "passive"))
      (node (ref "CN5") (pin "16") (pinfunction "VCCT_16") (pintype "power_in"))
      (node (ref "L23") (pin "2") (pinfunction "2_2") (pintype "passive"))
    )
    (net (code "81") (name "/VCCT_SFP_2") (class "Default")
      (node (ref "C208") (pin "1") (pinfunction "1_1") (pintype "passive"))
      (node (ref "C210") (pin "1") (pinfunction "1_1") (pintype "passive"))
      (node (ref "CN6") (pin "16") (pinfunction "VCCT_16") (pintype "power_in"))
      (node (ref "L24") (pin "2") (pinfunction "2_2") (pintype "passive"))
    )
    (net (code "82") (name "/VCCT_SFP_3") (class "Default")
      (node (ref "C223") (pin "1") (pinfunction "1_1") (pintype "passive"))
      (node (ref "C225") (pin "1") (pinfunction "1_1") (pintype "passive"))
      (node (ref "CN7") (pin "16") (pinfunction "VCCT_16") (pintype "power_in"))
      (node (ref "L27") (pin "2") (pinfunction "2_2") (pintype "passive"))
    )
    (net (code "83") (name "/VCCT_SFP_4") (class "Default")
      (node (ref "C224") (pin "1") (pinfunction "1_1") (pintype "passive"))
      (node (ref "C226") (pin "1") (pinfunction "1_1") (pintype "passive"))
      (node (ref "CN8") (pin "16") (pinfunction "VCCT_16") (pintype "power_in"))
      (node (ref "L28") (pin "2") (pinfunction "2_2") (pintype "passive"))
    )
    (net (code "84") (name "GND") (class "Default")
      (node (ref "C207") (pin "2") (pinfunction "2_2") (pintype "passive"))
      (node (ref "C208") (pin "2") (pinfunction "2_2") (pintype "passive"))
      (node (ref "C209") (pin "2") (pinfunction "2_2") (pintype "passive"))
      (node (ref "C210") (pin "2") (pinfunction "2_2") (pintype "passive"))
      (node (ref "C211") (pin "2") (pinfunction "2_2") (pintype "passive"))
      (node (ref "C212") (pin "2") (pinfunction "2_2") (pintype "passive"))
      (node (ref "C213") (pin "2") (pinfunction "2_2") (pintype "passive"))
      (node (ref "C214") (pin "2") (pinfunction "2_2") (pintype "passive"))
      (node (ref "C215") (pin "2") (pinfunction "2_2") (pintype "passive"))
      (node (ref "C216") (pin "2") (pinfunction "2_2") (pintype "passive"))
      (node (ref "C217") (pin "2") (pinfunction "2_2") (pintype "passive"))
      (node (ref "C218") (pin "2") (pinfunction "2_2") (pintype "passive"))
      (node (ref "C219") (pin "1") (pinfunction "1_1") (pintype "passive"))
      (node (ref "C220") (pin "2") (pinfunction "2_2") (pintype "passive"))
      (node (ref "C221") (pin "1") (pinfunction "1_1") (pintype "passive"))
      (node (ref "C222") (pin "2") (pinfunction "2_2") (pintype "passive"))
      (node (ref "C223") (pin "2") (pinfunction "2_2") (pintype "passive"))
      (node (ref "C224") (pin "2") (pinfunction "2_2") (pintype "passive"))
      (node (ref "C225") (pin "2") (pinfunction "2_2") (pintype "passive"))
      (node (ref "C226") (pin "2") (pinfunction "2_2") (pintype "passive"))
      (node (ref "C227") (pin "2") (pinfunction "2_2") (pintype "passive"))
      (node (ref "C228") (pin "2") (pinfunction "2_2") (pintype "passive"))
      (node (ref "C229") (pin "2") (pinfunction "2_2") (pintype "passive"))
      (node (ref "C230") (pin "2") (pinfunction "2_2") (pintype "passive"))
      (node (ref "C231") (pin "2") (pinfunction "2_2") (pintype "passive"))
      (node (ref "C232") (pin "2") (pinfunction "2_2") (pintype "passive"))
      (node (ref "C233") (pin "2") (pinfunction "2_2") (pintype "passive"))
      (node (ref "C234") (pin "2") (pinfunction "2_2") (pintype "passive"))
      (node (ref "C235") (pin "1") (pinfunction "1_1") (pintype "passive"))
      (node (ref "C236") (pin "2") (pinfunction "2_2") (pintype "passive"))
      (node (ref "C237") (pin "1") (pinfunction "1_1") (pintype "passive"))
      (node (ref "C238") (pin "2") (pinfunction "2_2") (pintype "passive"))
      (node (ref "CN5") (pin "1") (pinfunction "VEET_1") (pintype "power_in"))
      (node (ref "CN5") (pin "10") (pinfunction "VEER_10") (pintype "power_in"))
      (node (ref "CN5") (pin "11") (pinfunction "VEER_11") (pintype "power_in"))
      (node (ref "CN5") (pin "14") (pinfunction "VEER_14") (pintype "power_in"))
      (node (ref "CN5") (pin "17") (pinfunction "VEET_17") (pintype "power_in"))
      (node (ref "CN5") (pin "20") (pinfunction "VEET_20") (pintype "power_in"))
      (node (ref "CN5") (pin "21") (pinfunction "CAGE_21") (pintype "power_in"))
      (node (ref "CN5") (pin "22") (pinfunction "CAGE_22") (pintype "power_in"))
      (node (ref "CN5") (pin "23") (pinfunction "CAGE_23") (pintype "power_in"))
      (node (ref "CN5") (pin "24") (pinfunction "CAGE_24") (pintype "power_in"))
      (node (ref "CN5") (pin "25") (pinfunction "CAGE_25") (pintype "power_in"))
      (node (ref "CN5") (pin "26") (pinfunction "CAGE_26") (pintype "power_in"))
      (node (ref "CN5") (pin "27") (pinfunction "CAGE_27") (pintype "power_in"))
      (node (ref "CN5") (pin "28") (pinfunction "CAGE_28") (pintype "power_in"))
      (node (ref "CN5") (pin "29") (pinfunction "CAGE_29") (pintype "power_in"))
      (node (ref "CN5") (pin "30") (pinfunction "CAGE_30") (pintype "power_in"))
      (node (ref "CN5") (pin "31") (pinfunction "CAGE_31") (pintype "power_in"))
      (node (ref "CN5") (pin "32") (pinfunction "CAGE_32") (pintype "power_in"))
      (node (ref "CN5") (pin "33") (pinfunction "CAGE_33") (pintype "power_in"))
      (node (ref "CN5") (pin "34") (pinfunction "CAGE_34") (pintype "power_in"))
      (node (ref "CN5") (pin "35") (pinfunction "CAGE_35") (pintype "power_in"))
      (node (ref "CN5") (pin "36") (pinfunction "CAGE_36") (pintype "power_in"))
      (node (ref "CN5") (pin "37") (pinfunction "CAGE_37") (pintype "power_in"))
      (node (ref "CN5") (pin "38") (pinfunction "CAGE_38") (pintype "power_in"))
      (node (ref "CN5") (pin "39") (pinfunction "CAGE_39") (pintype "power_in"))
      (node (ref "CN5") (pin "40") (pinfunction "CAGE_40") (pintype "power_in"))
      (node (ref "CN6") (pin "1") (pinfunction "VEET_1") (pintype "power_in"))
      (node (ref "CN6") (pin "10") (pinfunction "VEER_10") (pintype "power_in"))
      (node (ref "CN6") (pin "11") (pinfunction "VEER_11") (pintype "power_in"))
      (node (ref "CN6") (pin "14") (pinfunction "VEER_14") (pintype "power_in"))
      (node (ref "CN6") (pin "17") (pinfunction "VEET_17") (pintype "power_in"))
      (node (ref "CN6") (pin "20") (pinfunction "VEET_20") (pintype "power_in"))
      (node (ref "CN6") (pin "21") (pinfunction "CAGE_21") (pintype "power_in"))
      (node (ref "CN6") (pin "22") (pinfunction "CAGE_22") (pintype "power_in"))
      (node (ref "CN6") (pin "23") (pinfunction "CAGE_23") (pintype "power_in"))
      (node (ref "CN6") (pin "24") (pinfunction "CAGE_24") (pintype "power_in"))
      (node (ref "CN6") (pin "25") (pinfunction "CAGE_25") (pintype "power_in"))
      (node (ref "CN6") (pin "26") (pinfunction "CAGE_26") (pintype "power_in"))
      (node (ref "CN6") (pin "27") (pinfunction "CAGE_27") (pintype "power_in"))
      (node (ref "CN6") (pin "28") (pinfunction "CAGE_28") (pintype "power_in"))
      (node (ref "CN6") (pin "29") (pinfunction "CAGE_29") (pintype "power_in"))
      (node (ref "CN6") (pin "30") (pinfunction "CAGE_30") (pintype "power_in"))
      (node (ref "CN6") (pin "31") (pinfunction "CAGE_31") (pintype "power_in"))
      (node (ref "CN6") (pin "32") (pinfunction "CAGE_32") (pintype "power_in"))
      (node (ref "CN6") (pin "33") (pinfunction "CAGE_33") (pintype "power_in"))
      (node (ref "CN6") (pin "34") (pinfunction "CAGE_34") (pintype "power_in"))
      (node (ref "CN6") (pin "35") (pinfunction "CAGE_35") (pintype "power_in"))
      (node (ref "CN6") (pin "36") (pinfunction "CAGE_36") (pintype "power_in"))
      (node (ref "CN6") (pin "37") (pinfunction "CAGE_37") (pintype "power_in"))
      (node (ref "CN6") (pin "38") (pinfunction "CAGE_38") (pintype "power_in"))
      (node (ref "CN6") (pin "39") (pinfunction "CAGE_39") (pintype "power_in"))
      (node (ref "CN6") (pin "40") (pinfunction "CAGE_40") (pintype "power_in"))
      (node (ref "CN7") (pin "1") (pinfunction "VEET_1") (pintype "power_in"))
      (node (ref "CN7") (pin "10") (pinfunction "VEER_10") (pintype "power_in"))
      (node (ref "CN7") (pin "11") (pinfunction "VEER_11") (pintype "power_in"))
      (node (ref "CN7") (pin "14") (pinfunction "VEER_14") (pintype "power_in"))
      (node (ref "CN7") (pin "17") (pinfunction "VEET_17") (pintype "power_in"))
      (node (ref "CN7") (pin "20") (pinfunction "VEET_20") (pintype "power_in"))
      (node (ref "CN7") (pin "21") (pinfunction "CAGE_21") (pintype "power_in"))
      (node (ref "CN7") (pin "22") (pinfunction "CAGE_22") (pintype "power_in"))
      (node (ref "CN7") (pin "23") (pinfunction "CAGE_23") (pintype "power_in"))
      (node (ref "CN7") (pin "24") (pinfunction "CAGE_24") (pintype "power_in"))
      (node (ref "CN7") (pin "25") (pinfunction "CAGE_25") (pintype "power_in"))
      (node (ref "CN7") (pin "26") (pinfunction "CAGE_26") (pintype "power_in"))
      (node (ref "CN7") (pin "27") (pinfunction "CAGE_27") (pintype "power_in"))
      (node (ref "CN7") (pin "28") (pinfunction "CAGE_28") (pintype "power_in"))
      (node (ref "CN7") (pin "29") (pinfunction "CAGE_29") (pintype "power_in"))
      (node (ref "CN7") (pin "30") (pinfunction "CAGE_30") (pintype "power_in"))
      (node (ref "CN7") (pin "31") (pinfunction "CAGE_31") (pintype "power_in"))
      (node (ref "CN7") (pin "32") (pinfunction "CAGE_32") (pintype "power_in"))
      (node (ref "CN7") (pin "33") (pinfunction "CAGE_33") (pintype "power_in"))
      (node (ref "CN7") (pin "34") (pinfunction "CAGE_34") (pintype "power_in"))
      (node (ref "CN7") (pin "35") (pinfunction "CAGE_35") (pintype "power_in"))
      (node (ref "CN7") (pin "36") (pinfunction "CAGE_36") (pintype "power_in"))
      (node (ref "CN7") (pin "37") (pinfunction "CAGE_37") (pintype "power_in"))
      (node (ref "CN7") (pin "38") (pinfunction "CAGE_38") (pintype "power_in"))
      (node (ref "CN7") (pin "39") (pinfunction "CAGE_39") (pintype "power_in"))
      (node (ref "CN7") (pin "40") (pinfunction "CAGE_40") (pintype "power_in"))
      (node (ref "CN8") (pin "1") (pinfunction "VEET_1") (pintype "power_in"))
      (node (ref "CN8") (pin "10") (pinfunction "VEER_10") (pintype "power_in"))
      (node (ref "CN8") (pin "11") (pinfunction "VEER_11") (pintype "power_in"))
      (node (ref "CN8") (pin "14") (pinfunction "VEER_14") (pintype "power_in"))
      (node (ref "CN8") (pin "17") (pinfunction "VEET_17") (pintype "power_in"))
      (node (ref "CN8") (pin "20") (pinfunction "VEET_20") (pintype "power_in"))
      (node (ref "CN8") (pin "21") (pinfunction "CAGE_21") (pintype "power_in"))
      (node (ref "CN8") (pin "22") (pinfunction "CAGE_22") (pintype "power_in"))
      (node (ref "CN8") (pin "23") (pinfunction "CAGE_23") (pintype "power_in"))
      (node (ref "CN8") (pin "24") (pinfunction "CAGE_24") (pintype "power_in"))
      (node (ref "CN8") (pin "25") (pinfunction "CAGE_25") (pintype "power_in"))
      (node (ref "CN8") (pin "26") (pinfunction "CAGE_26") (pintype "power_in"))
      (node (ref "CN8") (pin "27") (pinfunction "CAGE_27") (pintype "power_in"))
      (node (ref "CN8") (pin "28") (pinfunction "CAGE_28") (pintype "power_in"))
      (node (ref "CN8") (pin "29") (pinfunction "CAGE_29") (pintype "power_in"))
      (node (ref "CN8") (pin "30") (pinfunction "CAGE_30") (pintype "power_in"))
      (node (ref "CN8") (pin "31") (pinfunction "CAGE_31") (pintype "power_in"))
      (node (ref "CN8") (pin "32") (pinfunction "CAGE_32") (pintype "power_in"))
      (node (ref "CN8") (pin "33") (pinfunction "CAGE_33") (pintype "power_in"))
      (node (ref "CN8") (pin "34") (pinfunction "CAGE_34") (pintype "power_in"))
      (node (ref "CN8") (pin "35") (pinfunction "CAGE_35") (pintype "power_in"))
      (node (ref "CN8") (pin "36") (pinfunction "CAGE_36") (pintype "power_in"))
      (node (ref "CN8") (pin "37") (pinfunction "CAGE_37") (pintype "power_in"))
      (node (ref "CN8") (pin "38") (pinfunction "CAGE_38") (pintype "power_in"))
      (node (ref "CN8") (pin "39") (pinfunction "CAGE_39") (pintype "power_in"))
      (node (ref "CN8") (pin "40") (pinfunction "CAGE_40") (pintype "power_in"))
      (node (ref "R143") (pin "1") (pinfunction "1_1") (pintype "passive"))
      (node (ref "R144") (pin "1") (pinfunction "1_1") (pintype "passive"))
      (node (ref "R145") (pin "1") (pinfunction "1_1") (pintype "passive"))
      (node (ref "R146") (pin "1") (pinfunction "1_1") (pintype "passive"))
      (node (ref "R163") (pin "1") (pinfunction "1_1") (pintype "passive"))
      (node (ref "R164") (pin "1") (pinfunction "1_1") (pintype "passive"))
      (node (ref "R165") (pin "1") (pinfunction "1_1") (pintype "passive"))
      (node (ref "R166") (pin "1") (pinfunction "1_1") (pintype "passive"))
      (node (ref "U25") (pin "11") (pinfunction "GND_11") (pintype "power_in"))
      (node (ref "U26") (pin "11") (pinfunction "GND_11") (pintype "power_in"))
      (node (ref "U27") (pin "11") (pinfunction "GND_11") (pintype "power_in"))
      (node (ref "U28") (pin "11") (pinfunction "GND_11") (pintype "power_in"))
    )
    (net (code "85") (name "Net-(U25-OE)") (class "Default")
      (node (ref "R157") (pin "2") (pinfunction "2_2") (pintype "passive"))
      (node (ref "U25") (pin "10") (pinfunction "OE_10") (pintype "input"))
    )
    (net (code "86") (name "Net-(U26-OE)") (class "Default")
      (node (ref "R158") (pin "2") (pinfunction "2_2") (pintype "passive"))
      (node (ref "U26") (pin "10") (pinfunction "OE_10") (pintype "input"))
    )
    (net (code "87") (name "Net-(U27-OE)") (class "Default")
      (node (ref "R177") (pin "2") (pinfunction "2_2") (pintype "passive"))
      (node (ref "U27") (pin "10") (pinfunction "OE_10") (pintype "input"))
    )
    (net (code "88") (name "Net-(U28-OE)") (class "Default")
      (node (ref "R178") (pin "2") (pinfunction "2_2") (pintype "passive"))
      (node (ref "U28") (pin "10") (pinfunction "OE_10") (pintype "input"))
    )
    (net (code "89") (name "unconnected-(U25-A7-Pad8)") (class "Default")
      (node (ref "U25") (pin "8") (pinfunction "A7_8") (pintype "bidirectional+no_connect"))
    )
    (net (code "90") (name "unconnected-(U25-A8-Pad9)") (class "Default")
      (node (ref "U25") (pin "9") (pinfunction "A8_9") (pintype "bidirectional+no_connect"))
    )
    (net (code "91") (name "unconnected-(U25-B7-Pad13)") (class "Default")
      (node (ref "U25") (pin "13") (pinfunction "B7_13") (pintype "bidirectional+no_connect"))
    )
    (net (code "92") (name "unconnected-(U25-B8-Pad12)") (class "Default")
      (node (ref "U25") (pin "12") (pinfunction "B8_12") (pintype "bidirectional+no_connect"))
    )
    (net (code "93") (name "unconnected-(U26-A7-Pad8)") (class "Default")
      (node (ref "U26") (pin "8") (pinfunction "A7_8") (pintype "bidirectional+no_connect"))
    )
    (net (code "94") (name "unconnected-(U26-A8-Pad9)") (class "Default")
      (node (ref "U26") (pin "9") (pinfunction "A8_9") (pintype "bidirectional+no_connect"))
    )
    (net (code "95") (name "unconnected-(U26-B7-Pad13)") (class "Default")
      (node (ref "U26") (pin "13") (pinfunction "B7_13") (pintype "bidirectional+no_connect"))
    )
    (net (code "96") (name "unconnected-(U26-B8-Pad12)") (class "Default")
      (node (ref "U26") (pin "12") (pinfunction "B8_12") (pintype "bidirectional+no_connect"))
    )
    (net (code "97") (name "unconnected-(U27-A7-Pad8)") (class "Default")
      (node (ref "U27") (pin "8") (pinfunction "A7_8") (pintype "bidirectional+no_connect"))
    )
    (net (code "98") (name "unconnected-(U27-A8-Pad9)") (class "Default")
      (node (ref "U27") (pin "9") (pinfunction "A8_9") (pintype "bidirectional+no_connect"))
    )
    (net (code "99") (name "unconnected-(U27-B7-Pad13)") (class "Default")
      (node (ref "U27") (pin "13") (pinfunction "B7_13") (pintype "bidirectional+no_connect"))
    )
    (net (code "100") (name "unconnected-(U27-B8-Pad12)") (class "Default")
      (node (ref "U27") (pin "12") (pinfunction "B8_12") (pintype "bidirectional+no_connect"))
    )
    (net (code "101") (name "unconnected-(U28-A7-Pad8)") (class "Default")
      (node (ref "U28") (pin "8") (pinfunction "A7_8") (pintype "bidirectional+no_connect"))
    )
    (net (code "102") (name "unconnected-(U28-A8-Pad9)") (class "Default")
      (node (ref "U28") (pin "9") (pinfunction "A8_9") (pintype "bidirectional+no_connect"))
    )
    (net (code "103") (name "unconnected-(U28-B7-Pad13)") (class "Default")
      (node (ref "U28") (pin "13") (pinfunction "B7_13") (pintype "bidirectional+no_connect"))
    )
    (net (code "104") (name "unconnected-(U28-B8-Pad12)") (class "Default")
      (node (ref "U28") (pin "12") (pinfunction "B8_12") (pintype "bidirectional+no_connect"))
    )
  )
)
